# IOB-Outputs.net
KiCad netlist of a schematic drawn in EAGLE
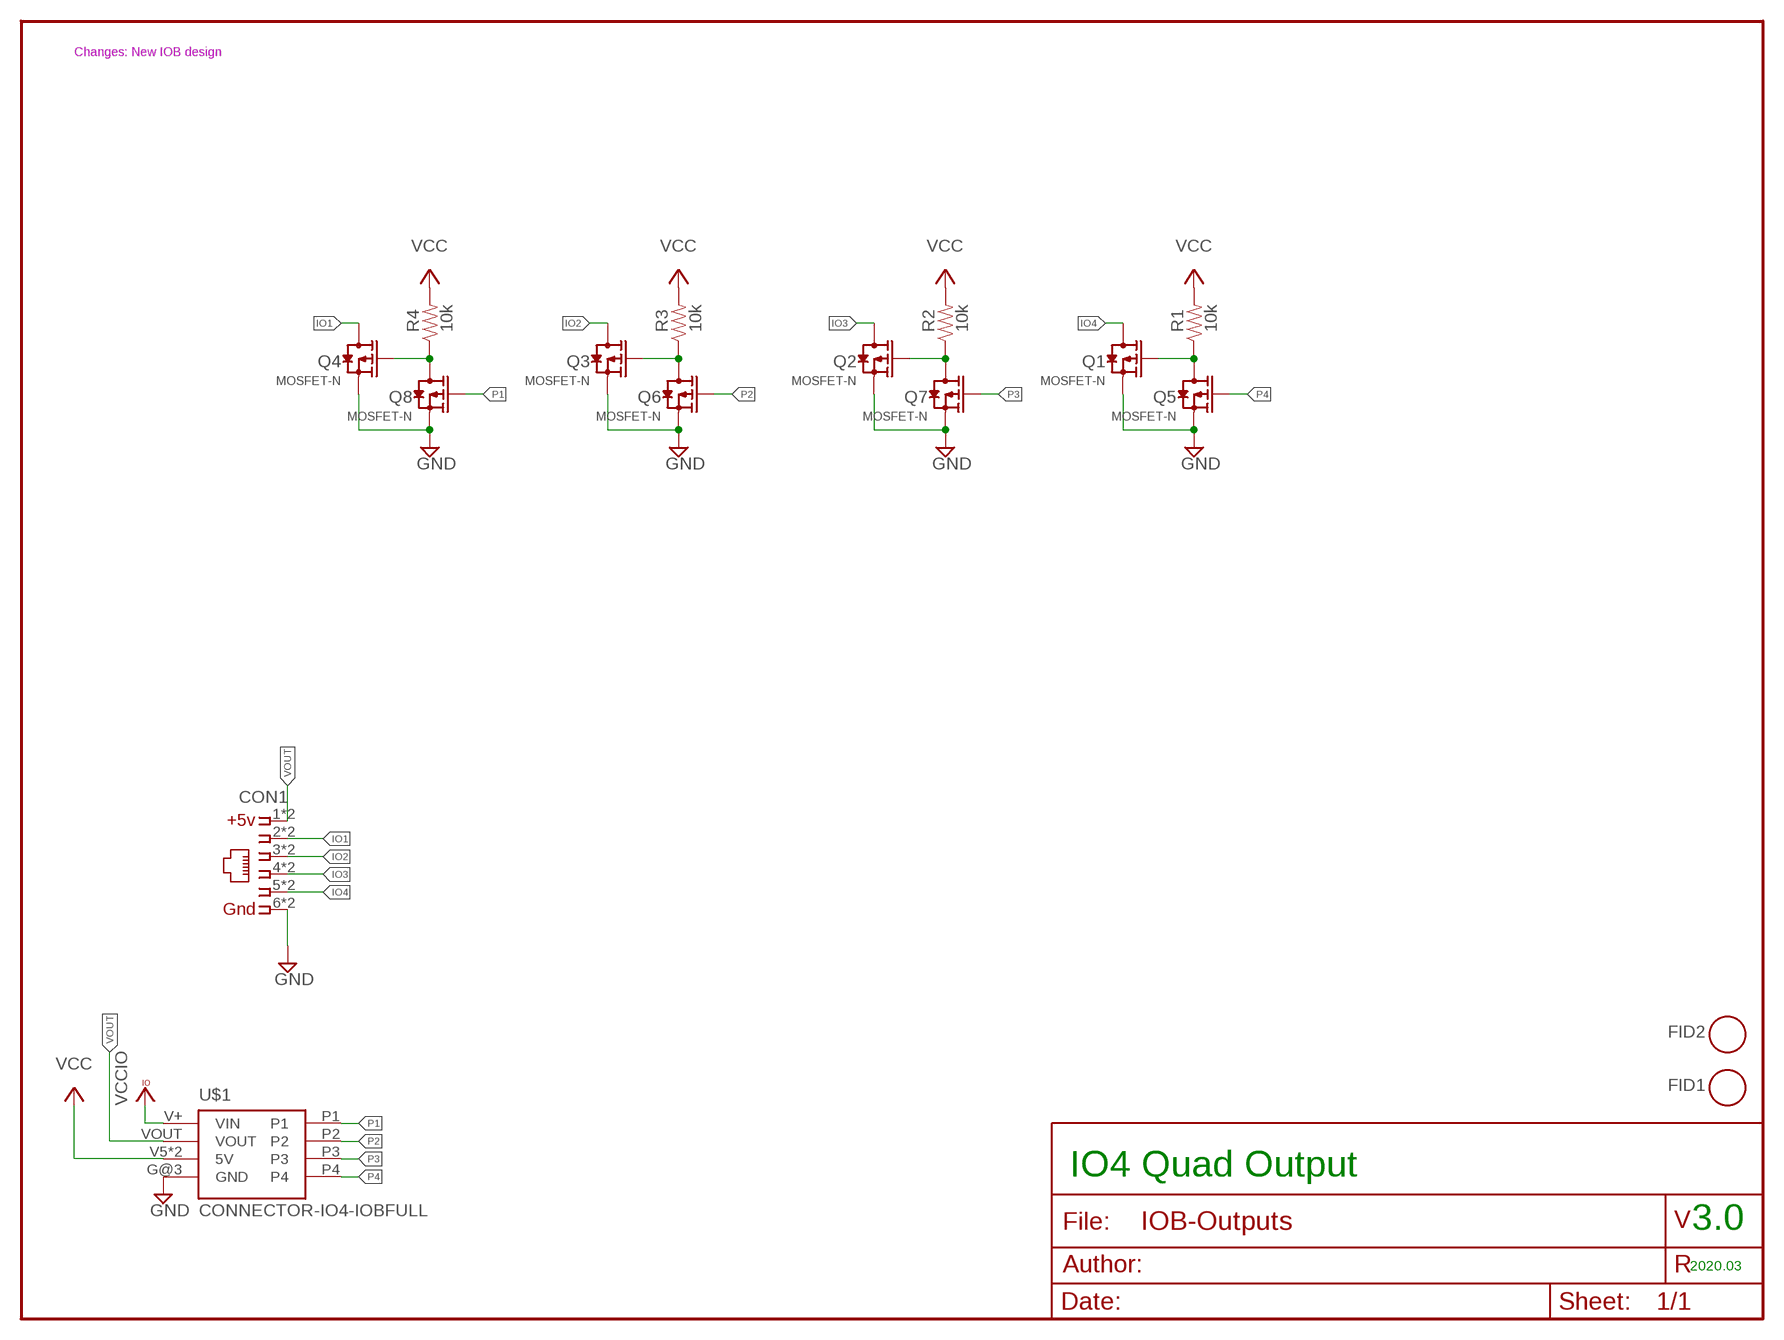
[diagram p0: schematic, sheet 1]

(export (version "E")
  (design (tool "Eeschema 10.0.6"))
  (components
    (comp (ref "CON1")
      (value "CONNECTOR-IO4IPINS")
      (footprint "eagle-import:RJ24-INVERTED-PINS")
      (libsource (lib "eagle-import") (part "CONNECTOR-IO4IPINS"))
    )
    (comp (ref "FID1")
      (value "FIDUCIAL")
      (footprint "eagle-import:FIDUCIAL_1MM")
      (libsource (lib "eagle-import") (part "FIDUCIAL"))
    )
    (comp (ref "FID2")
      (value "FIDUCIAL")
      (footprint "eagle-import:FIDUCIAL_1MM")
      (libsource (lib "eagle-import") (part "FIDUCIAL"))
    )
    (comp (ref "Q1")
      (value "MOSFET-N")
      (footprint "eagle-import:SOT23-3")
      (libsource (lib "eagle-import") (part "MOSFET-P"))
    )
    (comp (ref "Q2")
      (value "MOSFET-N")
      (footprint "eagle-import:SOT23-3")
      (libsource (lib "eagle-import") (part "MOSFET-P"))
    )
    (comp (ref "Q3")
      (value "MOSFET-N")
      (footprint "eagle-import:SOT23-3")
      (libsource (lib "eagle-import") (part "MOSFET-P"))
    )
    (comp (ref "Q4")
      (value "MOSFET-N")
      (footprint "eagle-import:SOT23-3")
      (libsource (lib "eagle-import") (part "MOSFET-P"))
    )
    (comp (ref "Q5")
      (value "MOSFET-N")
      (footprint "eagle-import:SOT23-3")
      (libsource (lib "eagle-import") (part "MOSFET-P"))
    )
    (comp (ref "Q6")
      (value "MOSFET-N")
      (footprint "eagle-import:SOT23-3")
      (libsource (lib "eagle-import") (part "MOSFET-P"))
    )
    (comp (ref "Q7")
      (value "MOSFET-N")
      (footprint "eagle-import:SOT23-3")
      (libsource (lib "eagle-import") (part "MOSFET-P"))
    )
    (comp (ref "Q8")
      (value "MOSFET-N")
      (footprint "eagle-import:SOT23-3")
      (libsource (lib "eagle-import") (part "MOSFET-P"))
    )
    (comp (ref "R1")
      (value "10k")
      (footprint "eagle-import:0805-RES")
      (libsource (lib "eagle-import") (part "R0805-RES"))
    )
    (comp (ref "R2")
      (value "10k")
      (footprint "eagle-import:0805-RES")
      (libsource (lib "eagle-import") (part "R0805-RES"))
    )
    (comp (ref "R3")
      (value "10k")
      (footprint "eagle-import:0805-RES")
      (libsource (lib "eagle-import") (part "R0805-RES"))
    )
    (comp (ref "R4")
      (value "10k")
      (footprint "eagle-import:0805-RES")
      (libsource (lib "eagle-import") (part "R0805-RES"))
    )
    (comp (ref "U$1")
      (value "CONNECTOR-IO4-IOBFULL")
      (footprint "eagle-import:IO4-IOB")
      (libsource (lib "eagle-import") (part "CONNECTOR-IO4-IOBFULL"))
    )
  )
  (nets
    (net (code "1") (name "GND") (class "Default")
      (node (ref "CON1") (pin "6") (pinfunction "6_6") (pintype "power_in"))
      (node (ref "CON1") (pin "6@1") (pinfunction "6_6@1") (pintype "power_in"))
      (node (ref "Q1") (pin "2") (pinfunction "S_2") (pintype "passive"))
      (node (ref "Q2") (pin "2") (pinfunction "S_2") (pintype "passive"))
      (node (ref "Q3") (pin "2") (pinfunction "S_2") (pintype "passive"))
      (node (ref "Q4") (pin "2") (pinfunction "S_2") (pintype "passive"))
      (node (ref "Q5") (pin "2") (pinfunction "S_2") (pintype "passive"))
      (node (ref "Q6") (pin "2") (pinfunction "S_2") (pintype "passive"))
      (node (ref "Q7") (pin "2") (pinfunction "S_2") (pintype "passive"))
      (node (ref "Q8") (pin "2") (pinfunction "S_2") (pintype "passive"))
      (node (ref "U$1") (pin "G@3") (pinfunction "GND_G@3") (pintype "power_in"))
    )
    (net (code "2") (name "IO1") (class "Default")
      (node (ref "CON1") (pin "2") (pinfunction "2_2") (pintype "passive"))
      (node (ref "CON1") (pin "2@1") (pinfunction "2_2@1") (pintype "passive"))
      (node (ref "Q4") (pin "3") (pinfunction "D_3") (pintype "passive"))
    )
    (net (code "3") (name "IO2") (class "Default")
      (node (ref "CON1") (pin "3") (pinfunction "3_3") (pintype "passive"))
      (node (ref "CON1") (pin "3@1") (pinfunction "3_3@1") (pintype "passive"))
      (node (ref "Q3") (pin "3") (pinfunction "D_3") (pintype "passive"))
    )
    (net (code "4") (name "IO3") (class "Default")
      (node (ref "CON1") (pin "4") (pinfunction "4_4") (pintype "passive"))
      (node (ref "CON1") (pin "4@1") (pinfunction "4_4@1") (pintype "passive"))
      (node (ref "Q2") (pin "3") (pinfunction "D_3") (pintype "passive"))
    )
    (net (code "5") (name "IO4") (class "Default")
      (node (ref "CON1") (pin "5") (pinfunction "5_5") (pintype "passive"))
      (node (ref "CON1") (pin "5@1") (pinfunction "5_5@1") (pintype "passive"))
      (node (ref "Q1") (pin "3") (pinfunction "D_3") (pintype "passive"))
    )
    (net (code "6") (name "Net-(Q1-G)") (class "Default")
      (node (ref "Q1") (pin "1") (pinfunction "G_1") (pintype "passive"))
      (node (ref "Q5") (pin "3") (pinfunction "D_3") (pintype "passive"))
      (node (ref "R1") (pin "1") (pinfunction "1_1") (pintype "passive"))
    )
    (net (code "7") (name "Net-(Q2-G)") (class "Default")
      (node (ref "Q2") (pin "1") (pinfunction "G_1") (pintype "passive"))
      (node (ref "Q7") (pin "3") (pinfunction "D_3") (pintype "passive"))
      (node (ref "R2") (pin "1") (pinfunction "1_1") (pintype "passive"))
    )
    (net (code "8") (name "Net-(Q3-G)") (class "Default")
      (node (ref "Q3") (pin "1") (pinfunction "G_1") (pintype "passive"))
      (node (ref "Q6") (pin "3") (pinfunction "D_3") (pintype "passive"))
      (node (ref "R3") (pin "1") (pinfunction "1_1") (pintype "passive"))
    )
    (net (code "9") (name "Net-(Q4-G)") (class "Default")
      (node (ref "Q4") (pin "1") (pinfunction "G_1") (pintype "passive"))
      (node (ref "Q8") (pin "3") (pinfunction "D_3") (pintype "passive"))
      (node (ref "R4") (pin "1") (pinfunction "1_1") (pintype "passive"))
    )
    (net (code "10") (name "P1") (class "Default")
      (node (ref "Q8") (pin "1") (pinfunction "G_1") (pintype "passive"))
      (node (ref "U$1") (pin "P1") (pinfunction "P1_P1") (pintype "bidirectional"))
    )
    (net (code "11") (name "P2") (class "Default")
      (node (ref "Q6") (pin "1") (pinfunction "G_1") (pintype "passive"))
      (node (ref "U$1") (pin "P2") (pinfunction "P2_P2") (pintype "bidirectional"))
    )
    (net (code "12") (name "P3") (class "Default")
      (node (ref "Q7") (pin "1") (pinfunction "G_1") (pintype "passive"))
      (node (ref "U$1") (pin "P3") (pinfunction "P3_P3") (pintype "bidirectional"))
    )
    (net (code "13") (name "P4") (class "Default")
      (node (ref "Q5") (pin "1") (pinfunction "G_1") (pintype "passive"))
      (node (ref "U$1") (pin "P4") (pinfunction "P4_P4") (pintype "bidirectional"))
    )
    (net (code "14") (name "VCC") (class "Default")
      (node (ref "R1") (pin "2") (pinfunction "2_2") (pintype "passive"))
      (node (ref "R2") (pin "2") (pinfunction "2_2") (pintype "passive"))
      (node (ref "R3") (pin "2") (pinfunction "2_2") (pintype "passive"))
      (node (ref "R4") (pin "2") (pinfunction "2_2") (pintype "passive"))
      (node (ref "U$1") (pin "V5") (pinfunction "5V_V5") (pintype "power_in"))
      (node (ref "U$1") (pin "V5@1") (pinfunction "5V_V5@1") (pintype "power_in"))
    )
    (net (code "15") (name "VCCIO") (class "Default")
      (node (ref "U$1") (pin "V+") (pinfunction "VIN_V+") (pintype "power_in"))
    )
    (net (code "16") (name "VOUT") (class "Default")
      (node (ref "CON1") (pin "1") (pinfunction "1_1") (pintype "power_in"))
      (node (ref "CON1") (pin "1@1") (pinfunction "1_1@1") (pintype "power_in"))
      (node (ref "U$1") (pin "VOUT") (pinfunction "VOUT_VOUT") (pintype "power_in"))
    )
  )
)
